# 549-team5.net
KiCad netlist of a schematic drawn in EAGLE
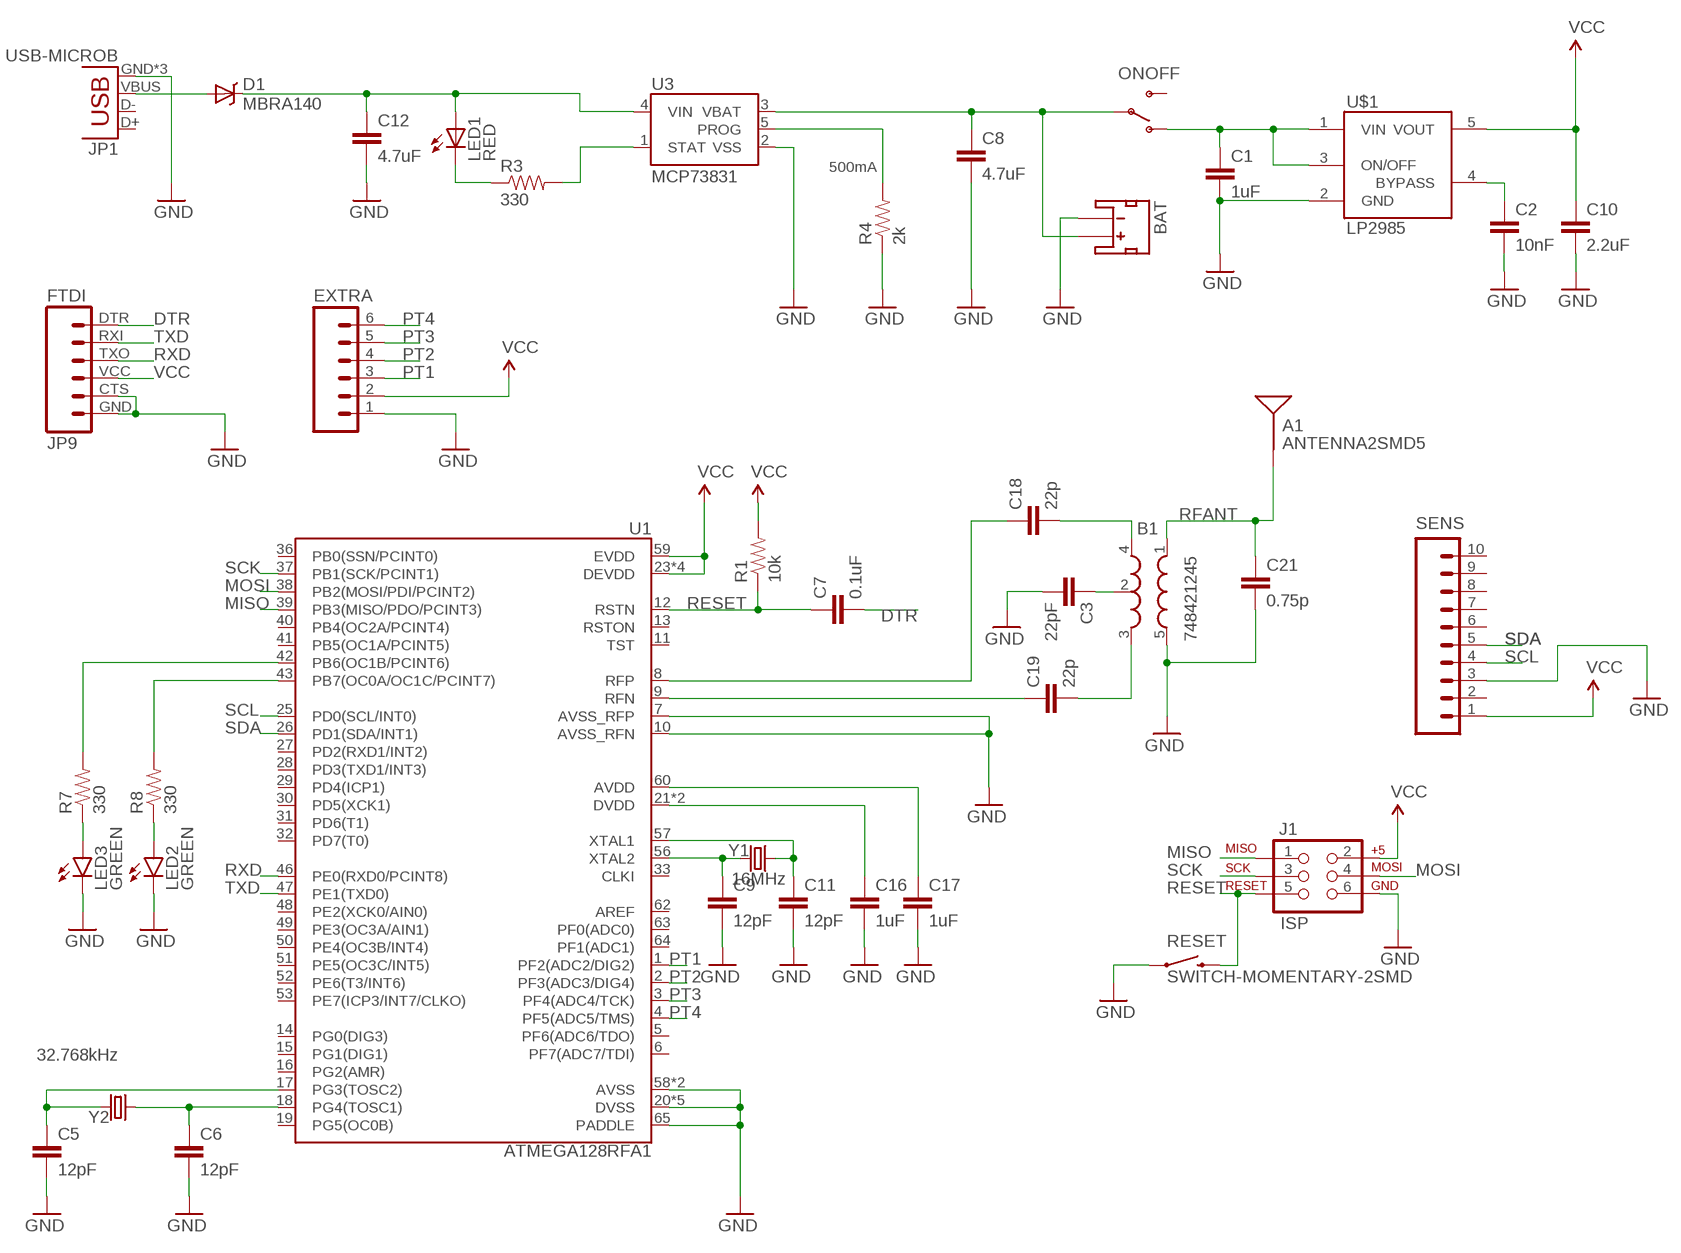
[diagram p0: schematic, sheet 1]

(export (version "E")
  (design (tool "Eeschema 10.0.6"))
  (components
    (comp (ref "A1")
      (value "ANTENNA2SMD5")
      (footprint "eagle-import:ANTENNA-CHIP5")
      (libsource (lib "eagle-import") (part "ANTENNA2SMD5"))
    )
    (comp (ref "B1")
      (value "748421245")
      (footprint "eagle-import:BALUN")
      (libsource (lib "eagle-import") (part "BALUN0805"))
    )
    (comp (ref "BAT")
      (value "JST_2MM_MALE")
      (footprint "eagle-import:JST-2-SMD")
      (libsource (lib "eagle-import") (part "JST_2MM_MALE"))
    )
    (comp (ref "C1")
      (value "1uF")
      (footprint "eagle-import:1206")
      (libsource (lib "eagle-import") (part "CAP1206"))
    )
    (comp (ref "C2")
      (value "10nF")
      (footprint "eagle-import:1206")
      (libsource (lib "eagle-import") (part "CAP1206"))
    )
    (comp (ref "C3")
      (value "22pF")
      (footprint "eagle-import:1206")
      (libsource (lib "eagle-import") (part "CAP1206"))
    )
    (comp (ref "C5")
      (value "12pF")
      (footprint "eagle-import:1206")
      (libsource (lib "eagle-import") (part "CAP1206"))
    )
    (comp (ref "C6")
      (value "12pF")
      (footprint "eagle-import:1206")
      (libsource (lib "eagle-import") (part "CAP1206"))
    )
    (comp (ref "C7")
      (value "0.1uF")
      (footprint "eagle-import:1206")
      (libsource (lib "eagle-import") (part "CAP1206"))
    )
    (comp (ref "C8")
      (value "4.7uF")
      (footprint "eagle-import:1206")
      (libsource (lib "eagle-import") (part "CAP1206"))
    )
    (comp (ref "C9")
      (value "12pF")
      (footprint "eagle-import:1206")
      (libsource (lib "eagle-import") (part "CAP1206"))
    )
    (comp (ref "C10")
      (value "2.2uF")
      (footprint "eagle-import:1206")
      (libsource (lib "eagle-import") (part "CAP1206"))
    )
    (comp (ref "C11")
      (value "12pF")
      (footprint "eagle-import:1206")
      (libsource (lib "eagle-import") (part "CAP1206"))
    )
    (comp (ref "C12")
      (value "4.7uF")
      (footprint "eagle-import:1206")
      (libsource (lib "eagle-import") (part "CAP1206"))
    )
    (comp (ref "C16")
      (value "1uF")
      (footprint "eagle-import:1206")
      (libsource (lib "eagle-import") (part "CAP1206"))
    )
    (comp (ref "C17")
      (value "1uF")
      (footprint "eagle-import:1206")
      (libsource (lib "eagle-import") (part "CAP1206"))
    )
    (comp (ref "C18")
      (value "22p")
      (footprint "eagle-import:1206")
      (libsource (lib "eagle-import") (part "CAP1206"))
    )
    (comp (ref "C19")
      (value "22p")
      (footprint "eagle-import:1206")
      (libsource (lib "eagle-import") (part "CAP1206"))
    )
    (comp (ref "C21")
      (value "0.75p")
      (footprint "eagle-import:1206")
      (libsource (lib "eagle-import") (part "CAP1206"))
    )
    (comp (ref "D1")
      (value "MBRA140")
      (footprint "eagle-import:SMA-DIODE")
      (libsource (lib "eagle-import") (part "MBRA140"))
    )
    (comp (ref "EXTRA")
      (value "M06SILK_FEMALE_PTH")
      (footprint "eagle-import:1X06")
      (libsource (lib "eagle-import") (part "M06SILK_FEMALE_PTH"))
    )
    (comp (ref "J1")
      (value "ISP")
      (footprint "eagle-import:2X3-NS")
      (libsource (lib "eagle-import") (part "AVR_SPI_PRG_6NS"))
    )
    (comp (ref "JP1")
      (value "USB-MICROB")
      (footprint "eagle-import:USB-MICROB")
      (libsource (lib "eagle-import") (part "USB-MICROB"))
    )
    (comp (ref "JP9")
      (value "FTDI")
      (footprint "eagle-import:FTDI_BASIC")
      (libsource (lib "eagle-import") (part "FTDI_BASICPTH"))
    )
    (comp (ref "LED1")
      (value "RED")
      (footprint "eagle-import:LED-1206")
      (libsource (lib "eagle-import") (part "LED1206"))
    )
    (comp (ref "LED2")
      (value "GREEN")
      (footprint "eagle-import:LED-1206")
      (libsource (lib "eagle-import") (part "SparkFun-LED_LED1206"))
    )
    (comp (ref "LED3")
      (value "GREEN")
      (footprint "eagle-import:LED-1206")
      (libsource (lib "eagle-import") (part "SparkFun-LED_LED1206"))
    )
    (comp (ref "ONOFF")
      (value "SWITCH-SPST-SMD-A")
      (footprint "eagle-import:SWITCH-SPST-SMD-A")
      (libsource (lib "eagle-import") (part "SWITCH-SPST-SMD-A"))
    )
    (comp (ref "R1")
      (value "10k")
      (footprint "eagle-import:1206")
      (libsource (lib "eagle-import") (part "RESISTOR1206"))
    )
    (comp (ref "R3")
      (value "330")
      (footprint "eagle-import:1206")
      (libsource (lib "eagle-import") (part "RESISTOR1206"))
    )
    (comp (ref "R4")
      (value "2k")
      (footprint "eagle-import:1206")
      (libsource (lib "eagle-import") (part "RESISTOR1206"))
    )
    (comp (ref "R7")
      (value "330")
      (footprint "eagle-import:1206")
      (libsource (lib "eagle-import") (part "RESISTOR1206"))
    )
    (comp (ref "R8")
      (value "330")
      (footprint "eagle-import:1206")
      (libsource (lib "eagle-import") (part "RESISTOR1206"))
    )
    (comp (ref "RESET")
      (value "SWITCH-MOMENTARY-2SMD")
      (footprint "eagle-import:TACTILE-SWITCH-SMD")
      (libsource (lib "eagle-import") (part "SWITCH-MOMENTARY-2SMD"))
    )
    (comp (ref "SENS")
      (value "M10SILK_FEMALE_PTH")
      (footprint "eagle-import:1X10")
      (libsource (lib "eagle-import") (part "M10SILK_FEMALE_PTH"))
    )
    (comp (ref "U$1")
      (value "LP2985AIM5-3.3")
      (footprint "eagle-import:SOT25")
      (libsource (lib "eagle-import") (part "LP2985AIM5-3.3"))
    )
    (comp (ref "U1")
      (value "ATMEGA128RFA1")
      (footprint "eagle-import:QFN-64")
      (libsource (lib "eagle-import") (part "ATMEGA128RFA1"))
    )
    (comp (ref "U3")
      (value "MCP73831")
      (footprint "eagle-import:SOT23-5")
      (libsource (lib "eagle-import") (part "MCP73831"))
    )
    (comp (ref "Y1")
      (value "16MHz")
      (footprint "eagle-import:CRYSTAL-SMD-5X3")
      (libsource (lib "eagle-import") (part "CRYSTAL5X3"))
    )
    (comp (ref "Y2")
      (value "32.768kHz")
      (footprint "eagle-import:CRYSTAL-32KHZ-SMD")
      (libsource (lib "eagle-import") (part "CRYSTAL32-SMD"))
    )
  )
  (nets
    (net (code "1") (name "/DTR") (class "Default")
      (node (ref "C7") (pin "2") (pinfunction "2_2") (pintype "passive"))
      (node (ref "JP9") (pin "DTR") (pinfunction "1_DTR") (pintype "passive"))
    )
    (net (code "2") (name "/MISO") (class "Default")
      (node (ref "J1") (pin "1") (pinfunction "1_1") (pintype "passive"))
      (node (ref "U1") (pin "39") (pinfunction "PB3(MISO/PDO/PCINT3)_39") (pintype "bidirectional"))
    )
    (net (code "3") (name "/MOSI") (class "Default")
      (node (ref "J1") (pin "4") (pinfunction "4_4") (pintype "passive"))
      (node (ref "U1") (pin "38") (pinfunction "PB2(MOSI/PDI/PCINT2)_38") (pintype "bidirectional"))
    )
    (net (code "4") (name "/PT1") (class "Default")
      (node (ref "EXTRA") (pin "3") (pinfunction "3_3") (pintype "passive"))
      (node (ref "U1") (pin "1") (pinfunction "PF2(ADC2/DIG2)_1") (pintype "bidirectional"))
    )
    (net (code "5") (name "/PT2") (class "Default")
      (node (ref "EXTRA") (pin "4") (pinfunction "4_4") (pintype "passive"))
      (node (ref "U1") (pin "2") (pinfunction "PF3(ADC3/DIG4)_2") (pintype "bidirectional"))
    )
    (net (code "6") (name "/PT3") (class "Default")
      (node (ref "EXTRA") (pin "5") (pinfunction "5_5") (pintype "passive"))
      (node (ref "U1") (pin "3") (pinfunction "PF4(ADC4/TCK)_3") (pintype "bidirectional"))
    )
    (net (code "7") (name "/PT4") (class "Default")
      (node (ref "EXTRA") (pin "6") (pinfunction "6_6") (pintype "passive"))
      (node (ref "U1") (pin "4") (pinfunction "PF5(ADC5/TMS)_4") (pintype "bidirectional"))
    )
    (net (code "8") (name "/RESET") (class "Default")
      (node (ref "C7") (pin "1") (pinfunction "1_1") (pintype "passive"))
      (node (ref "J1") (pin "5") (pinfunction "5_5") (pintype "passive"))
      (node (ref "R1") (pin "1") (pinfunction "1_1") (pintype "passive"))
      (node (ref "RESET") (pin "3") (pinfunction "2_3") (pintype "passive"))
      (node (ref "U1") (pin "12") (pinfunction "RSTN_12") (pintype "bidirectional"))
    )
    (net (code "9") (name "/RFANT") (class "Default")
      (node (ref "A1") (pin "FEED") (pinfunction "SIGNAL_FEED") (pintype "bidirectional"))
      (node (ref "B1") (pin "1") (pinfunction "IN_1") (pintype "bidirectional"))
      (node (ref "C21") (pin "1") (pinfunction "1_1") (pintype "passive"))
    )
    (net (code "10") (name "/RXD") (class "Default")
      (node (ref "JP9") (pin "TXO") (pinfunction "3_TXO") (pintype "passive"))
      (node (ref "U1") (pin "46") (pinfunction "PE0(RXD0/PCINT8)_46") (pintype "bidirectional"))
    )
    (net (code "11") (name "/SCK") (class "Default")
      (node (ref "J1") (pin "3") (pinfunction "3_3") (pintype "passive"))
      (node (ref "U1") (pin "37") (pinfunction "PB1(SCK/PCINT1)_37") (pintype "bidirectional"))
    )
    (net (code "12") (name "/SCL") (class "Default")
      (node (ref "SENS") (pin "4") (pinfunction "4_4") (pintype "passive"))
      (node (ref "U1") (pin "25") (pinfunction "PD0(SCL/INT0)_25") (pintype "bidirectional"))
    )
    (net (code "13") (name "/SDA") (class "Default")
      (node (ref "SENS") (pin "5") (pinfunction "5_5") (pintype "passive"))
      (node (ref "U1") (pin "26") (pinfunction "PD1(SDA/INT1)_26") (pintype "bidirectional"))
    )
    (net (code "14") (name "/TXD") (class "Default")
      (node (ref "JP9") (pin "RXI") (pinfunction "2_RXI") (pintype "passive"))
      (node (ref "U1") (pin "47") (pinfunction "PE1(TXD0)_47") (pintype "bidirectional"))
    )
    (net (code "15") (name "GND") (class "Default")
      (node (ref "B1") (pin "5") (pinfunction "GND_5") (pintype "bidirectional"))
      (node (ref "BAT") (pin "1") (pinfunction "-_1") (pintype "bidirectional"))
      (node (ref "C1") (pin "2") (pinfunction "2_2") (pintype "passive"))
      (node (ref "C10") (pin "2") (pinfunction "2_2") (pintype "passive"))
      (node (ref "C11") (pin "2") (pinfunction "2_2") (pintype "passive"))
      (node (ref "C12") (pin "2") (pinfunction "2_2") (pintype "passive"))
      (node (ref "C16") (pin "2") (pinfunction "2_2") (pintype "passive"))
      (node (ref "C17") (pin "2") (pinfunction "2_2") (pintype "passive"))
      (node (ref "C2") (pin "2") (pinfunction "2_2") (pintype "passive"))
      (node (ref "C21") (pin "2") (pinfunction "2_2") (pintype "passive"))
      (node (ref "C3") (pin "2") (pinfunction "2_2") (pintype "passive"))
      (node (ref "C5") (pin "2") (pinfunction "2_2") (pintype "passive"))
      (node (ref "C6") (pin "2") (pinfunction "2_2") (pintype "passive"))
      (node (ref "C8") (pin "2") (pinfunction "2_2") (pintype "passive"))
      (node (ref "C9") (pin "2") (pinfunction "2_2") (pintype "passive"))
      (node (ref "EXTRA") (pin "1") (pinfunction "1_1") (pintype "passive"))
      (node (ref "J1") (pin "6") (pinfunction "6_6") (pintype "passive"))
      (node (ref "JP1") (pin "GND") (pinfunction "GND_GND") (pintype "bidirectional"))
      (node (ref "JP1") (pin "MT1") (pinfunction "GND_MT1") (pintype "bidirectional"))
      (node (ref "JP1") (pin "MT2") (pinfunction "GND_MT2") (pintype "bidirectional"))
      (node (ref "JP9") (pin "CTS") (pinfunction "5_CTS") (pintype "passive"))
      (node (ref "JP9") (pin "GND") (pinfunction "6_GND") (pintype "passive"))
      (node (ref "LED2") (pin "C") (pinfunction "C_C") (pintype "passive"))
      (node (ref "LED3") (pin "C") (pinfunction "C_C") (pintype "passive"))
      (node (ref "R4") (pin "1") (pinfunction "1_1") (pintype "passive"))
      (node (ref "RESET") (pin "1") (pinfunction "1_1") (pintype "passive"))
      (node (ref "SENS") (pin "3") (pinfunction "3_3") (pintype "passive"))
      (node (ref "U$1") (pin "2") (pinfunction "GND_2") (pintype "power_in"))
      (node (ref "U1") (pin "10") (pinfunction "AVSS_RFN_10") (pintype "bidirectional"))
      (node (ref "U1") (pin "20") (pinfunction "DVSS_20") (pintype "bidirectional"))
      (node (ref "U1") (pin "24") (pinfunction "DVSS_24") (pintype "bidirectional"))
      (node (ref "U1") (pin "35") (pinfunction "DVSS_35") (pintype "bidirectional"))
      (node (ref "U1") (pin "45") (pinfunction "DVSS_45") (pintype "bidirectional"))
      (node (ref "U1") (pin "55") (pinfunction "DVSS_55") (pintype "bidirectional"))
      (node (ref "U1") (pin "58") (pinfunction "AVSS_58") (pintype "bidirectional"))
      (node (ref "U1") (pin "61") (pinfunction "AVSS_61") (pintype "bidirectional"))
      (node (ref "U1") (pin "65") (pinfunction "PADDLE_65") (pintype "bidirectional"))
      (node (ref "U1") (pin "7") (pinfunction "AVSS_RFP_7") (pintype "bidirectional"))
      (node (ref "U3") (pin "2") (pinfunction "VSS_2") (pintype "power_in"))
    )
    (net (code "16") (name "Net-(B1-GND-Pad2)") (class "Default")
      (node (ref "B1") (pin "2") (pinfunction "GND_2") (pintype "bidirectional"))
      (node (ref "C3") (pin "1") (pinfunction "1_1") (pintype "passive"))
    )
    (net (code "17") (name "Net-(B1-OUT1)") (class "Default")
      (node (ref "B1") (pin "4") (pinfunction "OUT1_4") (pintype "bidirectional"))
      (node (ref "C18") (pin "2") (pinfunction "2_2") (pintype "passive"))
    )
    (net (code "18") (name "Net-(B1-OUT2)") (class "Default")
      (node (ref "B1") (pin "3") (pinfunction "OUT2_3") (pintype "bidirectional"))
      (node (ref "C19") (pin "2") (pinfunction "2_2") (pintype "passive"))
    )
    (net (code "19") (name "Net-(BAT-+)") (class "Default")
      (node (ref "BAT") (pin "2") (pinfunction "+_2") (pintype "bidirectional"))
      (node (ref "C8") (pin "1") (pinfunction "1_1") (pintype "passive"))
      (node (ref "ONOFF") (pin "2") (pinfunction "P_2") (pintype "passive"))
      (node (ref "U3") (pin "3") (pinfunction "VBAT_3") (pintype "power_in"))
    )
    (net (code "20") (name "Net-(C16-Pad1)") (class "Default")
      (node (ref "C16") (pin "1") (pinfunction "1_1") (pintype "passive"))
      (node (ref "U1") (pin "21") (pinfunction "DVDD_21") (pintype "bidirectional"))
      (node (ref "U1") (pin "22") (pinfunction "DVDD_22") (pintype "bidirectional"))
    )
    (net (code "21") (name "Net-(D1-PadA)") (class "Default")
      (node (ref "D1") (pin "A") (pinfunction "A_A") (pintype "passive"))
      (node (ref "JP1") (pin "VBUS") (pinfunction "VBUS_VBUS") (pintype "bidirectional"))
    )
    (net (code "22") (name "Net-(LED1-PadC)") (class "Default")
      (node (ref "LED1") (pin "C") (pinfunction "C_C") (pintype "passive"))
      (node (ref "R3") (pin "1") (pinfunction "1_1") (pintype "passive"))
    )
    (net (code "23") (name "Net-(LED2-PadA)") (class "Default")
      (node (ref "LED2") (pin "A") (pinfunction "A_A") (pintype "passive"))
      (node (ref "R8") (pin "1") (pinfunction "1_1") (pintype "passive"))
    )
    (net (code "24") (name "Net-(LED3-PadA)") (class "Default")
      (node (ref "LED3") (pin "A") (pinfunction "A_A") (pintype "passive"))
      (node (ref "R7") (pin "1") (pinfunction "1_1") (pintype "passive"))
    )
    (net (code "25") (name "Net-(ONOFF-O)") (class "Default")
      (node (ref "C1") (pin "1") (pinfunction "1_1") (pintype "passive"))
      (node (ref "ONOFF") (pin "1") (pinfunction "O_1") (pintype "passive"))
      (node (ref "U$1") (pin "1") (pinfunction "VIN_1") (pintype "power_in"))
      (node (ref "U$1") (pin "3") (pinfunction "ON/OFF_3") (pintype "input"))
    )
    (net (code "26") (name "Net-(U$1-BYPASS)") (class "Default")
      (node (ref "C2") (pin "1") (pinfunction "1_1") (pintype "passive"))
      (node (ref "U$1") (pin "4") (pinfunction "BYPASS_4") (pintype "power_in"))
    )
    (net (code "27") (name "Net-(U1-AVDD)") (class "Default")
      (node (ref "C17") (pin "1") (pinfunction "1_1") (pintype "passive"))
      (node (ref "U1") (pin "60") (pinfunction "AVDD_60") (pintype "bidirectional"))
    )
    (net (code "28") (name "Net-(U1-PB6(OC1B{slash}PCINT6))") (class "Default")
      (node (ref "R7") (pin "2") (pinfunction "2_2") (pintype "passive"))
      (node (ref "U1") (pin "42") (pinfunction "PB6(OC1B/PCINT6)_42") (pintype "bidirectional"))
    )
    (net (code "29") (name "Net-(U1-PB7(OC0A{slash}OC1C{slash}PCINT7))") (class "Default")
      (node (ref "R8") (pin "2") (pinfunction "2_2") (pintype "passive"))
      (node (ref "U1") (pin "43") (pinfunction "PB7(OC0A/OC1C/PCINT7)_43") (pintype "bidirectional"))
    )
    (net (code "30") (name "Net-(U1-PG3(TOSC2))") (class "Default")
      (node (ref "C5") (pin "1") (pinfunction "1_1") (pintype "passive"))
      (node (ref "U1") (pin "17") (pinfunction "PG3(TOSC2)_17") (pintype "bidirectional"))
      (node (ref "Y2") (pin "X2") (pinfunction "2_X2") (pintype "passive"))
    )
    (net (code "31") (name "Net-(U1-PG4(TOSC1))") (class "Default")
      (node (ref "C6") (pin "1") (pinfunction "1_1") (pintype "passive"))
      (node (ref "U1") (pin "18") (pinfunction "PG4(TOSC1)_18") (pintype "bidirectional"))
      (node (ref "Y2") (pin "X1") (pinfunction "1_X1") (pintype "passive"))
    )
    (net (code "32") (name "Net-(U1-RFN)") (class "Default")
      (node (ref "C19") (pin "1") (pinfunction "1_1") (pintype "passive"))
      (node (ref "U1") (pin "9") (pinfunction "RFN_9") (pintype "bidirectional"))
    )
    (net (code "33") (name "Net-(U1-RFP)") (class "Default")
      (node (ref "C18") (pin "1") (pinfunction "1_1") (pintype "passive"))
      (node (ref "U1") (pin "8") (pinfunction "RFP_8") (pintype "bidirectional"))
    )
    (net (code "34") (name "Net-(U1-XTAL1)") (class "Default")
      (node (ref "C11") (pin "1") (pinfunction "1_1") (pintype "passive"))
      (node (ref "U1") (pin "57") (pinfunction "XTAL1_57") (pintype "bidirectional"))
      (node (ref "Y1") (pin "3") (pinfunction "2_3") (pintype "passive"))
    )
    (net (code "35") (name "Net-(U1-XTAL2)") (class "Default")
      (node (ref "C9") (pin "1") (pinfunction "1_1") (pintype "passive"))
      (node (ref "U1") (pin "56") (pinfunction "XTAL2_56") (pintype "bidirectional"))
      (node (ref "Y1") (pin "1") (pinfunction "1_1") (pintype "passive"))
    )
    (net (code "36") (name "Net-(U3-PROG)") (class "Default")
      (node (ref "R4") (pin "2") (pinfunction "2_2") (pintype "passive"))
      (node (ref "U3") (pin "5") (pinfunction "PROG_5") (pintype "input"))
    )
    (net (code "37") (name "Net-(U3-STAT)") (class "Default")
      (node (ref "R3") (pin "2") (pinfunction "2_2") (pintype "passive"))
      (node (ref "U3") (pin "1") (pinfunction "STAT_1") (pintype "output"))
    )
    (net (code "38") (name "Net-(U3-VIN)") (class "Default")
      (node (ref "C12") (pin "1") (pinfunction "1_1") (pintype "passive"))
      (node (ref "D1") (pin "C") (pinfunction "C_C") (pintype "passive"))
      (node (ref "LED1") (pin "A") (pinfunction "A_A") (pintype "passive"))
      (node (ref "U3") (pin "4") (pinfunction "VIN_4") (pintype "power_in"))
    )
    (net (code "39") (name "VCC") (class "Default")
      (node (ref "C10") (pin "1") (pinfunction "1_1") (pintype "passive"))
      (node (ref "EXTRA") (pin "2") (pinfunction "2_2") (pintype "passive"))
      (node (ref "J1") (pin "2") (pinfunction "2_2") (pintype "passive"))
      (node (ref "JP9") (pin "VCC") (pinfunction "4_VCC") (pintype "passive"))
      (node (ref "R1") (pin "2") (pinfunction "2_2") (pintype "passive"))
      (node (ref "SENS") (pin "1") (pinfunction "1_1") (pintype "passive"))
      (node (ref "U$1") (pin "5") (pinfunction "VOUT_5") (pintype "power_in"))
      (node (ref "U1") (pin "23") (pinfunction "DEVDD_23") (pintype "bidirectional"))
      (node (ref "U1") (pin "34") (pinfunction "DEVDD_34") (pintype "bidirectional"))
      (node (ref "U1") (pin "44") (pinfunction "DEVDD_44") (pintype "bidirectional"))
      (node (ref "U1") (pin "54") (pinfunction "DEVDD_54") (pintype "bidirectional"))
      (node (ref "U1") (pin "59") (pinfunction "EVDD_59") (pintype "bidirectional"))
    )
    (net (code "40") (name "unconnected-(BAT-PAD1-PadNC1)") (class "Default")
      (node (ref "BAT") (pin "NC1") (pinfunction "PAD1_NC1") (pintype "bidirectional"))
    )
    (net (code "41") (name "unconnected-(BAT-PAD2-PadNC2)") (class "Default")
      (node (ref "BAT") (pin "NC2") (pinfunction "PAD2_NC2") (pintype "bidirectional"))
    )
    (net (code "42") (name "unconnected-(JP1-PadD+)") (class "Default")
      (node (ref "JP1") (pin "D+") (pinfunction "D+_D+") (pintype "bidirectional"))
    )
    (net (code "43") (name "unconnected-(JP1-PadD-)") (class "Default")
      (node (ref "JP1") (pin "D-") (pinfunction "D-_D-") (pintype "bidirectional"))
    )
    (net (code "44") (name "unconnected-(ONOFF-S-Pad3)") (class "Default")
      (node (ref "ONOFF") (pin "3") (pinfunction "S_3") (pintype "passive"))
    )
    (net (code "45") (name "unconnected-(SENS-Pad2)") (class "Default")
      (node (ref "SENS") (pin "2") (pinfunction "2_2") (pintype "passive"))
    )
    (net (code "46") (name "unconnected-(SENS-Pad6)") (class "Default")
      (node (ref "SENS") (pin "6") (pinfunction "6_6") (pintype "passive"))
    )
    (net (code "47") (name "unconnected-(SENS-Pad7)") (class "Default")
      (node (ref "SENS") (pin "7") (pinfunction "7_7") (pintype "passive"))
    )
    (net (code "48") (name "unconnected-(SENS-Pad8)") (class "Default")
      (node (ref "SENS") (pin "8") (pinfunction "8_8") (pintype "passive"))
    )
    (net (code "49") (name "unconnected-(SENS-Pad9)") (class "Default")
      (node (ref "SENS") (pin "9") (pinfunction "9_9") (pintype "passive"))
    )
    (net (code "50") (name "unconnected-(SENS-Pad10)") (class "Default")
      (node (ref "SENS") (pin "10") (pinfunction "10_10") (pintype "passive"))
    )
    (net (code "51") (name "unconnected-(U1-AREF-Pad62)") (class "Default")
      (node (ref "U1") (pin "62") (pinfunction "AREF_62") (pintype "bidirectional"))
    )
    (net (code "52") (name "unconnected-(U1-CLKI-Pad33)") (class "Default")
      (node (ref "U1") (pin "33") (pinfunction "CLKI_33") (pintype "bidirectional"))
    )
    (net (code "53") (name "unconnected-(U1-PB0(SSN{slash}PCINT0)-Pad36)") (class "Default")
      (node (ref "U1") (pin "36") (pinfunction "PB0(SSN/PCINT0)_36") (pintype "bidirectional"))
    )
    (net (code "54") (name "unconnected-(U1-PB4(OC2A{slash}PCINT4)-Pad40)") (class "Default")
      (node (ref "U1") (pin "40") (pinfunction "PB4(OC2A/PCINT4)_40") (pintype "bidirectional"))
    )
    (net (code "55") (name "unconnected-(U1-PB5(OC1A{slash}PCINT5)-Pad41)") (class "Default")
      (node (ref "U1") (pin "41") (pinfunction "PB5(OC1A/PCINT5)_41") (pintype "bidirectional"))
    )
    (net (code "56") (name "unconnected-(U1-PD2(RXD1{slash}INT2)-Pad27)") (class "Default")
      (node (ref "U1") (pin "27") (pinfunction "PD2(RXD1/INT2)_27") (pintype "bidirectional"))
    )
    (net (code "57") (name "unconnected-(U1-PD3(TXD1{slash}INT3)-Pad28)") (class "Default")
      (node (ref "U1") (pin "28") (pinfunction "PD3(TXD1/INT3)_28") (pintype "bidirectional"))
    )
    (net (code "58") (name "unconnected-(U1-PD4(ICP1)-Pad29)") (class "Default")
      (node (ref "U1") (pin "29") (pinfunction "PD4(ICP1)_29") (pintype "bidirectional"))
    )
    (net (code "59") (name "unconnected-(U1-PD5(XCK1)-Pad30)") (class "Default")
      (node (ref "U1") (pin "30") (pinfunction "PD5(XCK1)_30") (pintype "bidirectional"))
    )
    (net (code "60") (name "unconnected-(U1-PD6(T1)-Pad31)") (class "Default")
      (node (ref "U1") (pin "31") (pinfunction "PD6(T1)_31") (pintype "bidirectional"))
    )
    (net (code "61") (name "unconnected-(U1-PD7(T0)-Pad32)") (class "Default")
      (node (ref "U1") (pin "32") (pinfunction "PD7(T0)_32") (pintype "bidirectional"))
    )
    (net (code "62") (name "unconnected-(U1-PE2(XCK0{slash}AIN0)-Pad48)") (class "Default")
      (node (ref "U1") (pin "48") (pinfunction "PE2(XCK0/AIN0)_48") (pintype "bidirectional"))
    )
    (net (code "63") (name "unconnected-(U1-PE3(OC3A{slash}AIN1)-Pad49)") (class "Default")
      (node (ref "U1") (pin "49") (pinfunction "PE3(OC3A/AIN1)_49") (pintype "bidirectional"))
    )
    (net (code "64") (name "unconnected-(U1-PE4(OC3B{slash}INT4)-Pad50)") (class "Default")
      (node (ref "U1") (pin "50") (pinfunction "PE4(OC3B/INT4)_50") (pintype "bidirectional"))
    )
    (net (code "65") (name "unconnected-(U1-PE5(OC3C{slash}INT5)-Pad51)") (class "Default")
      (node (ref "U1") (pin "51") (pinfunction "PE5(OC3C/INT5)_51") (pintype "bidirectional"))
    )
    (net (code "66") (name "unconnected-(U1-PE6(T3{slash}INT6)-Pad52)") (class "Default")
      (node (ref "U1") (pin "52") (pinfunction "PE6(T3/INT6)_52") (pintype "bidirectional"))
    )
    (net (code "67") (name "unconnected-(U1-PE7(ICP3{slash}INT7{slash}CLKO)-Pad53)") (class "Default")
      (node (ref "U1") (pin "53") (pinfunction "PE7(ICP3/INT7/CLKO)_53") (pintype "bidirectional"))
    )
    (net (code "68") (name "unconnected-(U1-PF0(ADC0)-Pad63)") (class "Default")
      (node (ref "U1") (pin "63") (pinfunction "PF0(ADC0)_63") (pintype "bidirectional"))
    )
    (net (code "69") (name "unconnected-(U1-PF1(ADC1)-Pad64)") (class "Default")
      (node (ref "U1") (pin "64") (pinfunction "PF1(ADC1)_64") (pintype "bidirectional"))
    )
    (net (code "70") (name "unconnected-(U1-PF6(ADC6{slash}TDO)-Pad5)") (class "Default")
      (node (ref "U1") (pin "5") (pinfunction "PF6(ADC6/TDO)_5") (pintype "bidirectional"))
    )
    (net (code "71") (name "unconnected-(U1-PF7(ADC7{slash}TDI)-Pad6)") (class "Default")
      (node (ref "U1") (pin "6") (pinfunction "PF7(ADC7/TDI)_6") (pintype "bidirectional"))
    )
    (net (code "72") (name "unconnected-(U1-PG0(DIG3)-Pad14)") (class "Default")
      (node (ref "U1") (pin "14") (pinfunction "PG0(DIG3)_14") (pintype "bidirectional"))
    )
    (net (code "73") (name "unconnected-(U1-PG1(DIG1)-Pad15)") (class "Default")
      (node (ref "U1") (pin "15") (pinfunction "PG1(DIG1)_15") (pintype "bidirectional"))
    )
    (net (code "74") (name "unconnected-(U1-PG2(AMR)-Pad16)") (class "Default")
      (node (ref "U1") (pin "16") (pinfunction "PG2(AMR)_16") (pintype "bidirectional"))
    )
    (net (code "75") (name "unconnected-(U1-PG5(OC0B)-Pad19)") (class "Default")
      (node (ref "U1") (pin "19") (pinfunction "PG5(OC0B)_19") (pintype "bidirectional"))
    )
    (net (code "76") (name "unconnected-(U1-RSTON-Pad13)") (class "Default")
      (node (ref "U1") (pin "13") (pinfunction "RSTON_13") (pintype "bidirectional"))
    )
    (net (code "77") (name "unconnected-(U1-TST-Pad11)") (class "Default")
      (node (ref "U1") (pin "11") (pinfunction "TST_11") (pintype "bidirectional"))
    )
  )
)
